# Motor_Connection.net
KiCad netlist of a schematic drawn in Altium Designer
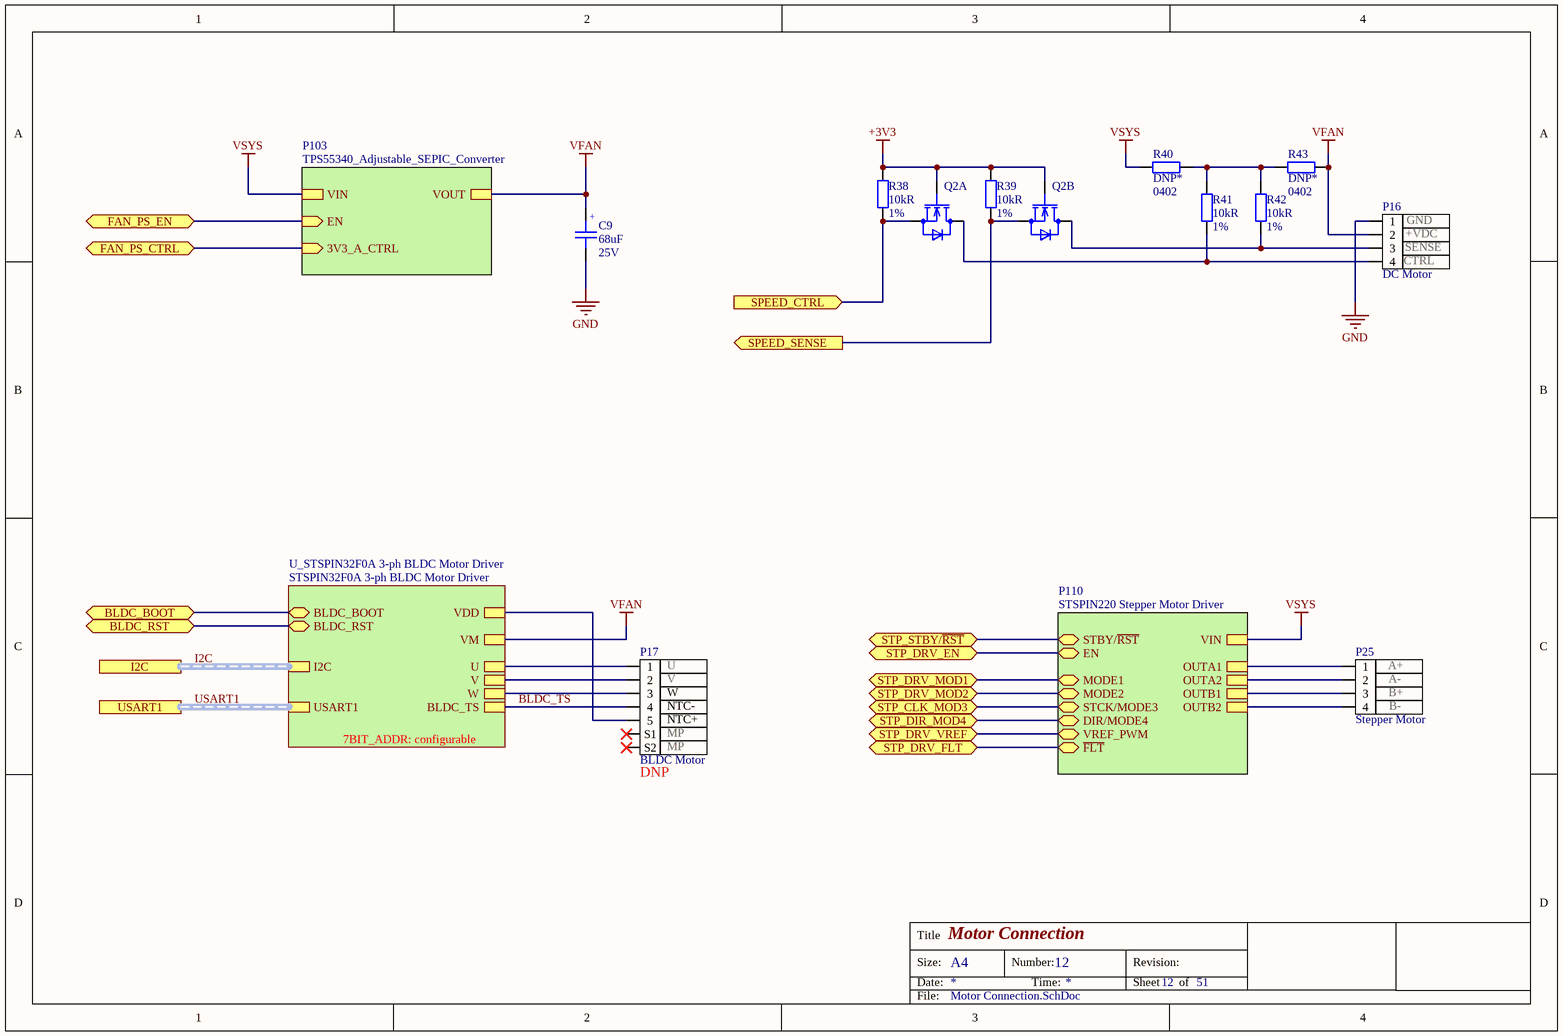
[diagram p0: Motor Connection.SchDoc]

(export (version "E")
  (design (tool "Eeschema 10.0.6"))
  (components
    (comp (ref "C9")
      (value "CAP TANT 68UF 20% 25V 2917")
      (footprint "CT7343")
      (description "68 µF Molded Tantalum Capacitors 25 V 2917 (7343 Metric) 200mOhm")
      (fields
        (field (name "MANUFACTURER") "KEMET")
        (field (name "MANUFACTURER PART NUMBER") "T495X686M025ATE200")
        (field (name "CAPACITANCE") "68uF")
        (field (name "RATED VOLTAGE") "25V")
      )
      (libsource (lib "Control_Board_Model") (part "CAP TANT 68UF 20% 25V 2917"))
    )
    (comp (ref "P16")
      (value "DC Motor")
      (footprint "CONN_JST_B4B-ZR-SM4-TF(LF)(SN)")
      (description "Connector Header Surface Mount 4 position 0.059\" (1.50mm)")
      (fields
        (field (name "MANUFACTURER") "JST")
        (field (name "MANUFACTURER PART NUMBER") "B4B-ZR-SM4-TFT(LF)(SN)")
        (field (name "PIN_1") "GND")
        (field (name "PIN_2") "+VDC")
        (field (name "PIN_3") "SENSE")
        (field (name "PIN_4") "CTRL")
      )
      (libsource (lib "Control_Board_Model") (part "CONN HEADER SMD 4POS 1.5MM"))
    )
    (comp (ref "P17")
      (value "BLDC Motor")
      (footprint "CONN_JST_B5B-PH-K-S(LF)(SN)")
      (description "Connector Header Through Hole 5 position 0.079\" (2.00mm)")
      (fields
        (field (name "MANUFACTURER") "JST")
        (field (name "MANUFACTURER PART NUMBER") "B5B-PH-K-S(LF)(SN)")
        (field (name "PIN_1") "U")
        (field (name "PIN_2") "V")
        (field (name "PIN_MP1") "MP")
        (field (name "PIN_MP2") "MP")
        (field (name "PIN_3") "W")
        (field (name "PIN_4") "NTC-")
        (field (name "PIN_5") "NTC+")
        (field (name "DNP STATUS") "DNP")
      )
      (libsource (lib "Control_Board_Model") (part "CONN HEADER VERT 5POS 2MM"))
    )
    (comp (ref "P25")
      (value "Stepper Motor")
      (footprint "CONN_JST_BM04B-NSHSS-TBT")
      (description "Connector Header Surface Mount 4 position 0.039\" (1.00mm)")
      (fields
        (field (name "MANUFACTURER") "JST")
        (field (name "MANUFACTURER PART NUMBER") "BM04B-NSHSS-TBT(LF)(SN)")
        (field (name "PIN_1") "A+")
        (field (name "PIN_2") "A-")
        (field (name "PIN_3") "B+")
        (field (name "PIN_4") "B-")
      )
      (libsource (lib "Control_Board_Model") (part "CONN HEADER SMD 4POS 1MM"))
    )
    (comp (ref "Q2")
      (value "DMN32D2LV-7")
      (footprint "SON_400UV-7_DIO")
      (description "Mosfet Array 2 N-Channel (Dual) 30V 400mA 400mW Surface Mount SOT-563")
      (fields (field (name "MANUFACTURER") "Diodes"))
      (libsource (lib "mosfets") (part "ARRAY MOSFET 2N-CH 30V 0.4A SOT-563"))
    )
    (comp (ref "R38")
      (value "RES SMD 10K OHM 1% 1/16W 0402")
      (footprint "R0402")
      (description "10 kOhms ±1% 0.063W, 1/16W Chip Resistor 0402 (1005 Metric) Moisture Resistant Thick Film")
      (fields
        (field (name "MANUFACTURER PART NUMBER") "RC0402FR-0710KP")
        (field (name "MANUFACTURER") "Yageo")
        (field (name "RESISTANCE") "10kR")
        (field (name "TOLERANCE") "1%")
      )
      (libsource (lib "resistors_smd") (part "RES SMD 10K OHM 1% 1/16W 0402"))
    )
    (comp (ref "R39")
      (value "RES SMD 10K OHM 1% 1/16W 0402")
      (footprint "R0402")
      (description "10 kOhms ±1% 0.063W, 1/16W Chip Resistor 0402 (1005 Metric) Moisture Resistant Thick Film")
      (fields
        (field (name "MANUFACTURER PART NUMBER") "RC0402FR-0710KP")
        (field (name "MANUFACTURER") "Yageo")
        (field (name "RESISTANCE") "10kR")
        (field (name "TOLERANCE") "1%")
      )
      (libsource (lib "resistors_smd") (part "RES SMD 10K OHM 1% 1/16W 0402"))
    )
    (comp (ref "R40")
      (value "DNP*")
      (footprint "R0402")
      (description "Placeholder for a 0402 resistor")
      (fields (field (name "CASE/PACKAGE") "0402"))
      (libsource (lib "resistors_smd") (part "RES SMD NO BOM 0402"))
    )
    (comp (ref "R41")
      (value "RES SMD 10K OHM 1% 1/16W 0402")
      (footprint "R0402")
      (description "10 kOhms ±1% 0.063W, 1/16W Chip Resistor 0402 (1005 Metric) Moisture Resistant Thick Film")
      (fields
        (field (name "MANUFACTURER PART NUMBER") "RC0402FR-0710KP")
        (field (name "MANUFACTURER") "Yageo")
        (field (name "RESISTANCE") "10kR")
        (field (name "TOLERANCE") "1%")
      )
      (libsource (lib "resistors_smd") (part "RES SMD 10K OHM 1% 1/16W 0402"))
    )
    (comp (ref "R42")
      (value "RES SMD 10K OHM 1% 1/16W 0402")
      (footprint "R0402")
      (description "10 kOhms ±1% 0.063W, 1/16W Chip Resistor 0402 (1005 Metric) Moisture Resistant Thick Film")
      (fields
        (field (name "MANUFACTURER PART NUMBER") "RC0402FR-0710KP")
        (field (name "MANUFACTURER") "Yageo")
        (field (name "RESISTANCE") "10kR")
        (field (name "TOLERANCE") "1%")
      )
      (libsource (lib "resistors_smd") (part "RES SMD 10K OHM 1% 1/16W 0402"))
    )
    (comp (ref "R43")
      (value "DNP*")
      (footprint "R0402")
      (description "Placeholder for a 0402 resistor")
      (fields (field (name "CASE/PACKAGE") "0402"))
      (libsource (lib "resistors_smd") (part "RES SMD NO BOM 0402"))
    )
  )
  (nets
    (net (code "3") (name "+3V3") (class "Default")
      (node (ref "Q2") (pin "2") (pinfunction "G_2") (pintype "passive"))
      (node (ref "Q2") (pin "5") (pinfunction "G_5") (pintype "passive"))
      (node (ref "R38") (pin "1") (pinfunction "1_1") (pintype "passive"))
      (node (ref "R39") (pin "1") (pinfunction "1_1") (pintype "passive"))
    )
    (net (code "6") (name "/BLDC_TS") (class "Default")
      (node (ref "P17") (pin "4") (pinfunction "4_4") (pintype "passive"))
    )
    (net (code "9") (name "/OUTA1") (class "Default")
      (node (ref "P25") (pin "1") (pinfunction "1_1") (pintype "passive"))
    )
    (net (code "10") (name "/OUTA2") (class "Default")
      (node (ref "P25") (pin "2") (pinfunction "2_2") (pintype "passive"))
    )
    (net (code "11") (name "/OUTB1") (class "Default")
      (node (ref "P25") (pin "3") (pinfunction "3_3") (pintype "passive"))
    )
    (net (code "12") (name "/OUTB2") (class "Default")
      (node (ref "P25") (pin "4") (pinfunction "4_4") (pintype "passive"))
    )
    (net (code "13") (name "/SPEED_CTRL") (class "Default")
      (node (ref "Q2") (pin "1") (pinfunction "S_1") (pintype "passive"))
      (node (ref "R38") (pin "2") (pinfunction "2_2") (pintype "passive"))
    )
    (net (code "14") (name "/SPEED_SENSE") (class "Default")
      (node (ref "Q2") (pin "4") (pinfunction "S_4") (pintype "passive"))
      (node (ref "R39") (pin "2") (pinfunction "2_2") (pintype "passive"))
    )
    (net (code "23") (name "/U") (class "Default")
      (node (ref "P17") (pin "1") (pinfunction "1_1") (pintype "passive"))
    )
    (net (code "24") (name "/V") (class "Default")
      (node (ref "P17") (pin "2") (pinfunction "2_2") (pintype "passive"))
    )
    (net (code "25") (name "/VDD") (class "Default")
      (node (ref "P17") (pin "5") (pinfunction "5_5") (pintype "passive"))
    )
    (net (code "26") (name "/W") (class "Default")
      (node (ref "P17") (pin "3") (pinfunction "3_3") (pintype "passive"))
    )
    (net (code "29") (name "GND") (class "Default")
      (node (ref "C9") (pin "2") (pinfunction "2_2") (pintype "passive"))
      (node (ref "P16") (pin "1") (pinfunction "1_1") (pintype "passive"))
    )
    (net (code "30") (name "Net-(Q2A-D)") (class "Default")
      (node (ref "P16") (pin "4") (pinfunction "4_4") (pintype "passive"))
      (node (ref "Q2") (pin "6") (pinfunction "D_6") (pintype "passive"))
      (node (ref "R41") (pin "2") (pinfunction "2_2") (pintype "passive"))
    )
    (net (code "31") (name "Net-(Q2B-D)") (class "Default")
      (node (ref "P16") (pin "3") (pinfunction "3_3") (pintype "passive"))
      (node (ref "Q2") (pin "3") (pinfunction "D_3") (pintype "passive"))
      (node (ref "R42") (pin "2") (pinfunction "2_2") (pintype "passive"))
    )
    (net (code "32") (name "Net-(R40-Pad2)") (class "Default")
      (node (ref "R40") (pin "2") (pinfunction "2_2") (pintype "passive"))
      (node (ref "R41") (pin "1") (pinfunction "1_1") (pintype "passive"))
      (node (ref "R42") (pin "1") (pinfunction "1_1") (pintype "passive"))
      (node (ref "R43") (pin "1") (pinfunction "1_1") (pintype "passive"))
    )
    (net (code "33") (name "VFAN") (class "Default")
      (node (ref "C9") (pin "1") (pinfunction "1_1") (pintype "passive"))
      (node (ref "P16") (pin "2") (pinfunction "2_2") (pintype "passive"))
      (node (ref "R43") (pin "2") (pinfunction "2_2") (pintype "passive"))
    )
    (net (code "34") (name "VSYS") (class "Default")
      (node (ref "R40") (pin "1") (pinfunction "1_1") (pintype "passive"))
    )
    (net (code "35") (name "unconnected-(P17-PadS1)") (class "Default")
      (node (ref "P17") (pin "S1") (pinfunction "S1_S1") (pintype "passive+no_connect"))
    )
    (net (code "36") (name "unconnected-(P17-PadS2)") (class "Default")
      (node (ref "P17") (pin "S2") (pinfunction "S2_S2") (pintype "passive+no_connect"))
    )
  )
)
